# Schematic_IR_encoder_v2.net
KiCad netlist of a schematic drawn in Altium Designer
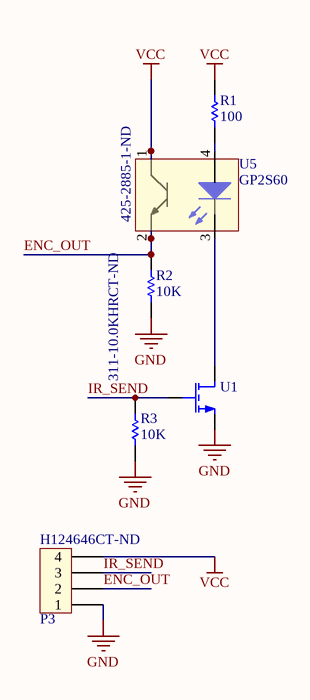
[diagram p0: Schematic_IR_encoder_v2.SchDoc]

(export (version "E")
  (design (tool "Eeschema 10.0.6"))
  (components
    (comp (ref "P3")
      (value "FH33J-4S-0.5SH(99)")
      (footprint "FH33J-4S-0.5SH(99)")
      (description "0.5mm FPC connector")
      (fields
        (field (name "DIGIKEY PART NUMBER") "H124646CT-ND")
        (field (name "SUPPLIER PART NUMBER 1") "H124646CT-ND")
        (field (name "MANUFACTURER") "Hirose Electric Co Ltd")
      )
      (libsource (lib "Artem_Library") (part "FH33J-4S-0.5SH(99)"))
    )
    (comp (ref "R1") (value "100") (footprint "0603W") (libsource (lib "Artem_Library") (part "Resistor")))
    (comp (ref "R2")
      (value "10K")
      (footprint "0603W")
      (fields (field (name "SUPPLIER PART NUMBER 1") "311-10.0KHRCT-ND"))
      (libsource (lib "Artem_Library") (part "Resistor"))
    )
    (comp (ref "R3") (value "10K") (footprint "0603W") (libsource (lib "Artem_Library") (part "Resistor")))
    (comp (ref "U1")
      (value "MOSFET N CHANNEL")
      (footprint "SOT323")
      (fields (field (name "DIGIKEY PART NUMBER") "568-5987-1-ND"))
      (libsource (lib "Artem_Library") (part "MOSFET N CHANNEL"))
    )
    (comp (ref "U5")
      (value "GP2S60")
      (footprint "GP2S60")
      (fields
        (field (name "DIGIKEY PART NUMBER") "425-2885-1-ND")
        (field (name "SUPPLIER PART NUMBER 1") "425-2885-1-ND")
      )
      (libsource (lib "Artem_Library") (part "GP2S60"))
    )
  )
  (nets
    (net (code "1") (name "/ENC_OUT") (class "Default")
      (node (ref "P3") (pin "2") (pinfunction "2_2") (pintype "passive"))
      (node (ref "R2") (pin "2") (pinfunction "2_2") (pintype "passive"))
      (node (ref "U5") (pin "2") (pinfunction "2_2") (pintype "passive"))
    )
    (net (code "2") (name "/IR_SEND") (class "Default")
      (node (ref "P3") (pin "3") (pinfunction "3_3") (pintype "passive"))
      (node (ref "R3") (pin "2") (pinfunction "2_2") (pintype "passive"))
      (node (ref "U1") (pin "1") (pinfunction "G_1") (pintype "passive"))
    )
    (net (code "3") (name "GND") (class "Default")
      (node (ref "P3") (pin "1") (pinfunction "1_1") (pintype "passive"))
      (node (ref "R2") (pin "1") (pinfunction "1_1") (pintype "passive"))
      (node (ref "R3") (pin "1") (pinfunction "1_1") (pintype "passive"))
      (node (ref "U1") (pin "2") (pinfunction "S_2") (pintype "passive"))
    )
    (net (code "4") (name "Net-(R1-Pad1)") (class "Default")
      (node (ref "R1") (pin "1") (pinfunction "1_1") (pintype "passive"))
      (node (ref "U5") (pin "4") (pinfunction "4_4") (pintype "passive"))
    )
    (net (code "5") (name "Net-(U1-D)") (class "Default")
      (node (ref "U1") (pin "3") (pinfunction "D_3") (pintype "passive"))
      (node (ref "U5") (pin "3") (pinfunction "3_3") (pintype "passive"))
    )
    (net (code "6") (name "VCC") (class "Default")
      (node (ref "P3") (pin "4") (pinfunction "4_4") (pintype "passive"))
      (node (ref "R1") (pin "2") (pinfunction "2_2") (pintype "passive"))
      (node (ref "U5") (pin "1") (pinfunction "1_1") (pintype "passive"))
    )
  )
)
